# cuisine.net
KiCad netlist of a schematic drawn in EAGLE
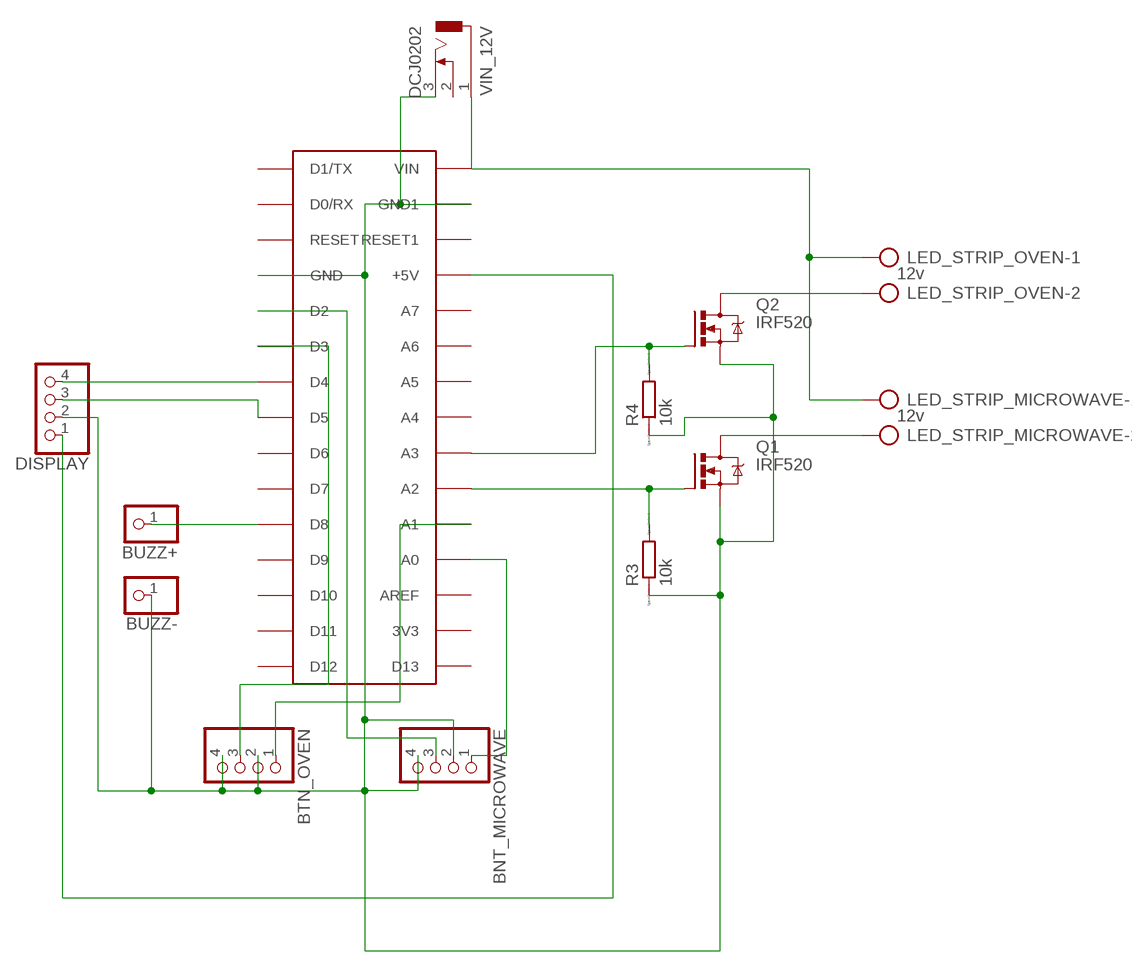
[diagram p0: schematic, sheet 1]

(export (version "E")
  (design (tool "Eeschema 10.0.6"))
  (components
    (comp (ref "BNT_MICROWAVE")
      (value "PINHD-1X4")
      (footprint "eagle-import:1X04")
      (libsource (lib "eagle-import") (part "PINHD-1X4"))
    )
    (comp (ref "BTN_OVEN")
      (value "PINHD-1X4")
      (footprint "eagle-import:1X04")
      (libsource (lib "eagle-import") (part "PINHD-1X4"))
    )
    (comp (ref "BUZZ+")
      (value "PINHD-1X1")
      (footprint "eagle-import:1X01")
      (libsource (lib "eagle-import") (part "PINHD-1X1"))
    )
    (comp (ref "BUZZ-")
      (value "PINHD-1X1")
      (footprint "eagle-import:1X01")
      (libsource (lib "eagle-import") (part "PINHD-1X1"))
    )
    (comp (ref "DISPLAY")
      (value "PINHD-1X4")
      (footprint "eagle-import:1X04")
      (libsource (lib "eagle-import") (part "PINHD-1X4"))
    )
    (comp (ref "LED_STRIP_MICROWAVE")
      (value "12v")
      (footprint "eagle-import:AK500_2")
      (libsource (lib "eagle-import") (part "AK500/2"))
    )
    (comp (ref "LED_STRIP_OVEN")
      (value "12v")
      (footprint "eagle-import:AK500_2")
      (libsource (lib "eagle-import") (part "AK500/2"))
    )
    (comp (ref "NANO")
      (value "ARDUINONANO")
      (footprint "eagle-import:PDIP-32")
      (libsource (lib "eagle-import") (part "ARDUINONANO"))
    )
    (comp (ref "Q1")
      (value "IRF520")
      (footprint "eagle-import:TO220BV")
      (libsource (lib "eagle-import") (part "IRF520"))
    )
    (comp (ref "Q2")
      (value "IRF520")
      (footprint "eagle-import:TO220BV")
      (libsource (lib "eagle-import") (part "IRF520"))
    )
    (comp (ref "R3")
      (value "10k")
      (footprint "eagle-import:0204_7")
      (libsource (lib "eagle-import") (part "R0204/7"))
    )
    (comp (ref "R4")
      (value "10k")
      (footprint "eagle-import:0204_7")
      (libsource (lib "eagle-import") (part "R0204/7"))
    )
    (comp (ref "VIN_12V")
      (value "DCJ0202")
      (footprint "eagle-import:DCJ0202")
      (libsource (lib "eagle-import") (part "DCJ0202"))
    )
  )
  (nets
    (net (code "1") (name "Net-(BNT_MICROWAVE-Pad1)") (class "Default")
      (node (ref "BNT_MICROWAVE") (pin "1") (pinfunction "1_1") (pintype "passive"))
      (node (ref "NANO") (pin "A0") (pinfunction "A0_A0") (pintype "bidirectional"))
    )
    (net (code "2") (name "Net-(BNT_MICROWAVE-Pad2)") (class "Default")
      (node (ref "BNT_MICROWAVE") (pin "2") (pinfunction "2_2") (pintype "passive"))
      (node (ref "BNT_MICROWAVE") (pin "4") (pinfunction "4_4") (pintype "passive"))
      (node (ref "BTN_OVEN") (pin "2") (pinfunction "2_2") (pintype "passive"))
      (node (ref "BTN_OVEN") (pin "4") (pinfunction "4_4") (pintype "passive"))
      (node (ref "BUZZ-") (pin "1") (pinfunction "1_1") (pintype "passive"))
      (node (ref "DISPLAY") (pin "2") (pinfunction "2_2") (pintype "passive"))
      (node (ref "NANO") (pin "GND") (pinfunction "GND_GND") (pintype "bidirectional"))
      (node (ref "NANO") (pin "GND1") (pinfunction "GND1_GND1") (pintype "bidirectional"))
      (node (ref "Q1") (pin "S") (pinfunction "S_S") (pintype "passive"))
      (node (ref "Q2") (pin "S") (pinfunction "S_S") (pintype "passive"))
      (node (ref "R3") (pin "1") (pinfunction "1_1") (pintype "passive"))
      (node (ref "R4") (pin "1") (pinfunction "1_1") (pintype "passive"))
      (node (ref "VIN_12V") (pin "3") (pinfunction "3_3") (pintype "passive"))
    )
    (net (code "3") (name "Net-(BNT_MICROWAVE-Pad3)") (class "Default")
      (node (ref "BNT_MICROWAVE") (pin "3") (pinfunction "3_3") (pintype "passive"))
      (node (ref "NANO") (pin "D2") (pinfunction "D2_D2") (pintype "bidirectional"))
    )
    (net (code "4") (name "Net-(BTN_OVEN-Pad1)") (class "Default")
      (node (ref "BTN_OVEN") (pin "1") (pinfunction "1_1") (pintype "passive"))
      (node (ref "NANO") (pin "A1") (pinfunction "A1_A1") (pintype "bidirectional"))
    )
    (net (code "5") (name "Net-(BTN_OVEN-Pad3)") (class "Default")
      (node (ref "BTN_OVEN") (pin "3") (pinfunction "3_3") (pintype "passive"))
      (node (ref "NANO") (pin "D3") (pinfunction "D3_D3") (pintype "bidirectional"))
    )
    (net (code "6") (name "Net-(BUZZ+-Pad1)") (class "Default")
      (node (ref "BUZZ+") (pin "1") (pinfunction "1_1") (pintype "passive"))
      (node (ref "NANO") (pin "D8") (pinfunction "D8_D8") (pintype "bidirectional"))
    )
    (net (code "7") (name "Net-(DISPLAY-Pad1)") (class "Default")
      (node (ref "DISPLAY") (pin "1") (pinfunction "1_1") (pintype "passive"))
      (node (ref "NANO") (pin "+5V") (pinfunction "+5V_+5V") (pintype "bidirectional"))
    )
    (net (code "8") (name "Net-(DISPLAY-Pad3)") (class "Default")
      (node (ref "DISPLAY") (pin "3") (pinfunction "3_3") (pintype "passive"))
      (node (ref "NANO") (pin "D5") (pinfunction "D5_D5") (pintype "bidirectional"))
    )
    (net (code "9") (name "Net-(DISPLAY-Pad4)") (class "Default")
      (node (ref "DISPLAY") (pin "4") (pinfunction "4_4") (pintype "passive"))
      (node (ref "NANO") (pin "D4") (pinfunction "D4_D4") (pintype "bidirectional"))
    )
    (net (code "10") (name "Net-(LED_STRIP_MICROWAVEA-KL)") (class "Default")
      (node (ref "LED_STRIP_MICROWAVE") (pin "1") (pinfunction "KL_1") (pintype "passive"))
      (node (ref "LED_STRIP_OVEN") (pin "1") (pinfunction "KL_1") (pintype "passive"))
      (node (ref "NANO") (pin "VIN") (pinfunction "VIN_VIN") (pintype "bidirectional"))
      (node (ref "VIN_12V") (pin "1") (pinfunction "1_1") (pintype "passive"))
    )
    (net (code "11") (name "Net-(LED_STRIP_MICROWAVEB-KL)") (class "Default")
      (node (ref "LED_STRIP_MICROWAVE") (pin "2") (pinfunction "KL_2") (pintype "passive"))
      (node (ref "Q1") (pin "D") (pinfunction "D_D") (pintype "passive"))
    )
    (net (code "12") (name "Net-(LED_STRIP_OVENB-KL)") (class "Default")
      (node (ref "LED_STRIP_OVEN") (pin "2") (pinfunction "KL_2") (pintype "passive"))
      (node (ref "Q2") (pin "D") (pinfunction "D_D") (pintype "passive"))
    )
    (net (code "13") (name "Net-(NANO-PadA2)") (class "Default")
      (node (ref "NANO") (pin "A2") (pinfunction "A2_A2") (pintype "bidirectional"))
      (node (ref "Q1") (pin "G") (pinfunction "G_G") (pintype "passive"))
      (node (ref "R3") (pin "2") (pinfunction "2_2") (pintype "passive"))
    )
    (net (code "14") (name "Net-(NANO-PadA3)") (class "Default")
      (node (ref "NANO") (pin "A3") (pinfunction "A3_A3") (pintype "bidirectional"))
      (node (ref "Q2") (pin "G") (pinfunction "G_G") (pintype "passive"))
      (node (ref "R4") (pin "2") (pinfunction "2_2") (pintype "passive"))
    )
    (net (code "15") (name "unconnected-(NANO-Pad3V3)") (class "Default")
      (node (ref "NANO") (pin "3V3") (pinfunction "3V3_3V3") (pintype "bidirectional"))
    )
    (net (code "16") (name "unconnected-(NANO-PadA4)") (class "Default")
      (node (ref "NANO") (pin "A4") (pinfunction "A4_A4") (pintype "bidirectional"))
    )
    (net (code "17") (name "unconnected-(NANO-PadA5)") (class "Default")
      (node (ref "NANO") (pin "A5") (pinfunction "A5_A5") (pintype "bidirectional"))
    )
    (net (code "18") (name "unconnected-(NANO-PadA6)") (class "Default")
      (node (ref "NANO") (pin "A6") (pinfunction "A6_A6") (pintype "bidirectional"))
    )
    (net (code "19") (name "unconnected-(NANO-PadA7)") (class "Default")
      (node (ref "NANO") (pin "A7") (pinfunction "A7_A7") (pintype "bidirectional"))
    )
    (net (code "20") (name "unconnected-(NANO-PadAREF)") (class "Default")
      (node (ref "NANO") (pin "AREF") (pinfunction "AREF_AREF") (pintype "bidirectional"))
    )
    (net (code "21") (name "unconnected-(NANO-PadD0{slash}RX)") (class "Default")
      (node (ref "NANO") (pin "D0/RX") (pinfunction "D0/RX_D0/RX") (pintype "bidirectional"))
    )
    (net (code "22") (name "unconnected-(NANO-PadD1{slash}TX)") (class "Default")
      (node (ref "NANO") (pin "D1/TX") (pinfunction "D1/TX_D1/TX") (pintype "bidirectional"))
    )
    (net (code "23") (name "unconnected-(NANO-PadD6)") (class "Default")
      (node (ref "NANO") (pin "D6") (pinfunction "D6_D6") (pintype "bidirectional"))
    )
    (net (code "24") (name "unconnected-(NANO-PadD7)") (class "Default")
      (node (ref "NANO") (pin "D7") (pinfunction "D7_D7") (pintype "bidirectional"))
    )
    (net (code "25") (name "unconnected-(NANO-PadD9)") (class "Default")
      (node (ref "NANO") (pin "D9") (pinfunction "D9_D9") (pintype "bidirectional"))
    )
    (net (code "26") (name "unconnected-(NANO-PadD10)") (class "Default")
      (node (ref "NANO") (pin "D10") (pinfunction "D10_D10") (pintype "bidirectional"))
    )
    (net (code "27") (name "unconnected-(NANO-PadD11)") (class "Default")
      (node (ref "NANO") (pin "D11") (pinfunction "D11_D11") (pintype "bidirectional"))
    )
    (net (code "28") (name "unconnected-(NANO-PadD12)") (class "Default")
      (node (ref "NANO") (pin "D12") (pinfunction "D12_D12") (pintype "bidirectional"))
    )
    (net (code "29") (name "unconnected-(NANO-PadD13)") (class "Default")
      (node (ref "NANO") (pin "D13") (pinfunction "D13_D13") (pintype "bidirectional"))
    )
    (net (code "30") (name "unconnected-(NANO-PadRESET)") (class "Default")
      (node (ref "NANO") (pin "RESET") (pinfunction "RESET_RESET") (pintype "bidirectional"))
    )
    (net (code "31") (name "unconnected-(NANO-PadRESET1)") (class "Default")
      (node (ref "NANO") (pin "RESET1") (pinfunction "RESET1_RESET1") (pintype "bidirectional"))
    )
    (net (code "32") (name "unconnected-(VIN_12V-Pad2)") (class "Default")
      (node (ref "VIN_12V") (pin "2") (pinfunction "2_2") (pintype "passive"))
    )
  )
)
